# triac.net
KiCad netlist of a schematic drawn in EAGLE
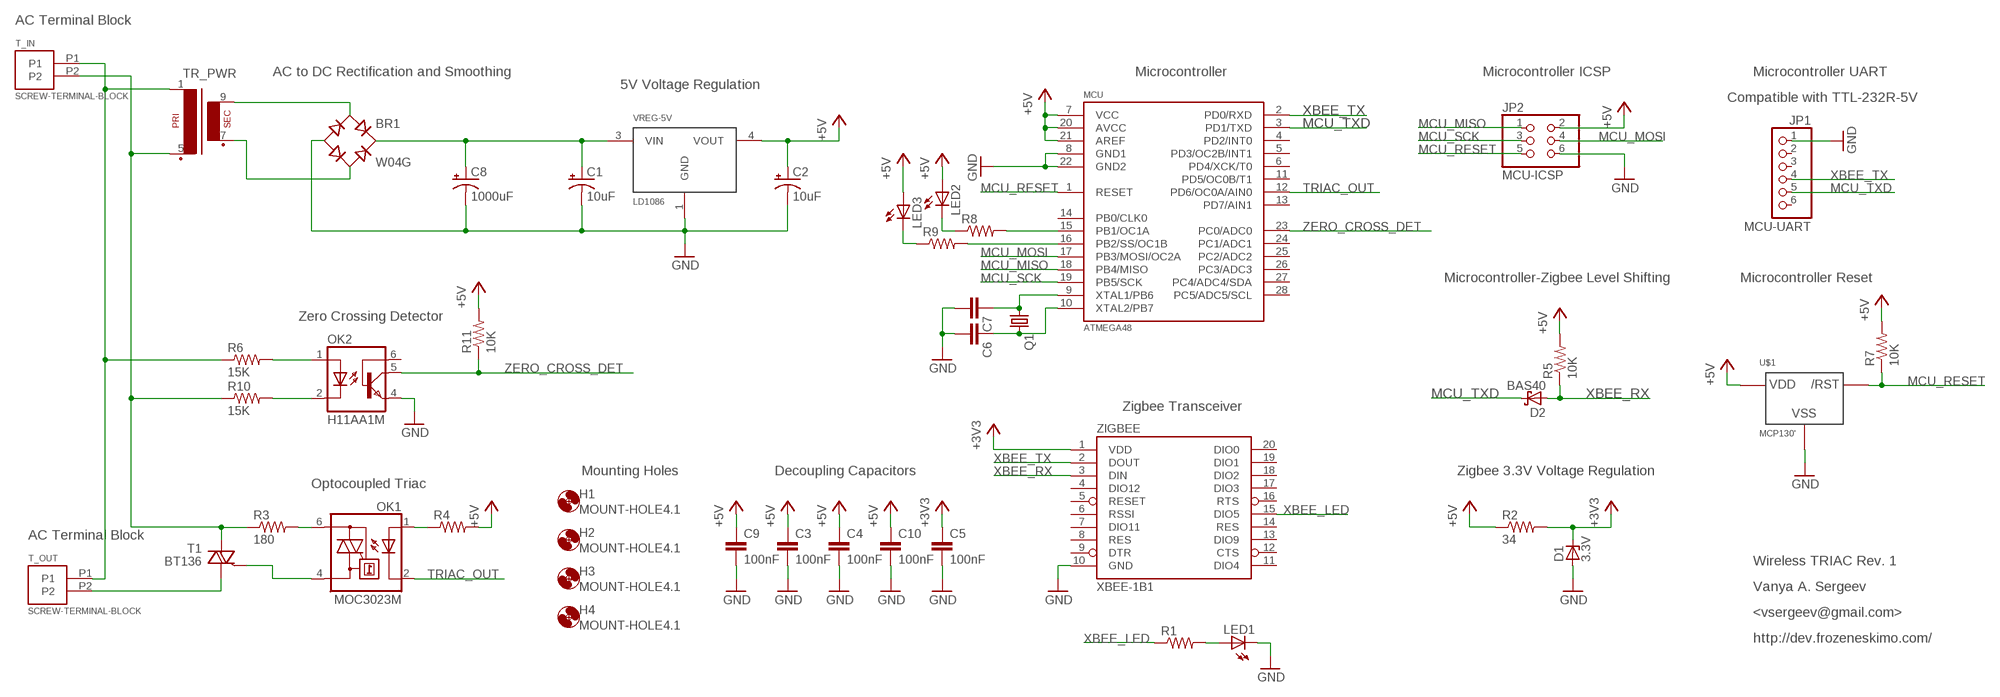
[diagram p0: schematic, sheet 1]

(export (version "E")
  (design (tool "Eeschema 10.0.6"))
  (components
    (comp (ref "BR1")
      (value "W04G")
      (footprint "eagle-import:WOG")
      (libsource (lib "eagle-import") (part "WG04"))
    )
    (comp (ref "C1")
      (value "10uF")
      (footprint "eagle-import:E2,5-5")
      (libsource (lib "eagle-import") (part "CPOL-USE2.5-5"))
    )
    (comp (ref "C2")
      (value "10uF")
      (footprint "eagle-import:E2,5-5")
      (libsource (lib "eagle-import") (part "CPOL-USE2.5-5"))
    )
    (comp (ref "C3")
      (value "100nF")
      (footprint "eagle-import:C0805")
      (libsource (lib "eagle-import") (part "C-EUC0805"))
    )
    (comp (ref "C4")
      (value "100nF")
      (footprint "eagle-import:C0805")
      (libsource (lib "eagle-import") (part "C-EUC0805"))
    )
    (comp (ref "C5")
      (value "100nF")
      (footprint "eagle-import:C0805")
      (libsource (lib "eagle-import") (part "C-EUC0805"))
    )
    (comp (ref "C6")
      (value "C-EUC0805")
      (footprint "eagle-import:C0805")
      (libsource (lib "eagle-import") (part "C-EUC0805"))
    )
    (comp (ref "C7")
      (value "C-EUC0805")
      (footprint "eagle-import:C0805")
      (libsource (lib "eagle-import") (part "C-EUC0805"))
    )
    (comp (ref "C8")
      (value "1000uF")
      (footprint "eagle-import:E5-13")
      (libsource (lib "eagle-import") (part "CPOL-USE5-13"))
    )
    (comp (ref "C9")
      (value "100nF")
      (footprint "eagle-import:C0805")
      (libsource (lib "eagle-import") (part "C-EUC0805"))
    )
    (comp (ref "C10")
      (value "100nF")
      (footprint "eagle-import:C0805")
      (libsource (lib "eagle-import") (part "C-EUC0805"))
    )
    (comp (ref "D1")
      (value "3.3V")
      (footprint "eagle-import:SOT23")
      (libsource (lib "eagle-import") (part "ZENER-DIODESOT23"))
    )
    (comp (ref "D2")
      (value "BAS40")
      (footprint "eagle-import:SOT23")
      (libsource (lib "eagle-import") (part "BAS40"))
    )
    (comp (ref "H1")
      (value "MOUNT-HOLE4.1")
      (footprint "eagle-import:4,1")
      (libsource (lib "eagle-import") (part "MOUNT-HOLE4.1"))
    )
    (comp (ref "H2")
      (value "MOUNT-HOLE4.1")
      (footprint "eagle-import:4,1")
      (libsource (lib "eagle-import") (part "MOUNT-HOLE4.1"))
    )
    (comp (ref "H3")
      (value "MOUNT-HOLE4.1")
      (footprint "eagle-import:4,1")
      (libsource (lib "eagle-import") (part "MOUNT-HOLE4.1"))
    )
    (comp (ref "H4")
      (value "MOUNT-HOLE4.1")
      (footprint "eagle-import:4,1")
      (libsource (lib "eagle-import") (part "MOUNT-HOLE4.1"))
    )
    (comp (ref "JP1")
      (value "MCU-UART")
      (footprint "eagle-import:1X06")
      (libsource (lib "eagle-import") (part "PINHD-1X6"))
    )
    (comp (ref "JP2")
      (value "MCU-ICSP")
      (footprint "eagle-import:2X03")
      (libsource (lib "eagle-import") (part "PINHD-2X3"))
    )
    (comp (ref "LED1")
      (value "LEDCHIPLED_0805")
      (footprint "eagle-import:CHIPLED_0805")
      (libsource (lib "eagle-import") (part "LEDCHIPLED_0805"))
    )
    (comp (ref "LED2")
      (value "LEDCHIPLED_0805")
      (footprint "eagle-import:CHIPLED_0805")
      (libsource (lib "eagle-import") (part "LEDCHIPLED_0805"))
    )
    (comp (ref "LED3")
      (value "LEDCHIPLED_0805")
      (footprint "eagle-import:CHIPLED_0805")
      (libsource (lib "eagle-import") (part "LEDCHIPLED_0805"))
    )
    (comp (ref "MCU")
      (value "ATMEGA48")
      (footprint "eagle-import:DIL28-3")
      (libsource (lib "eagle-import") (part "ATMEGA48"))
    )
    (comp (ref "OK1")
      (value "MOC3023M")
      (footprint "eagle-import:DIL06")
      (libsource (lib "eagle-import") (part "MOC30M23"))
    )
    (comp (ref "OK2")
      (value "H11AA1M")
      (footprint "eagle-import:DIL06")
      (libsource (lib "eagle-import") (part "H11A?M1"))
    )
    (comp (ref "Q1")
      (value "CRYSTALHC49UP")
      (footprint "eagle-import:HC49UP")
      (libsource (lib "eagle-import") (part "CRYSTALHC49UP"))
    )
    (comp (ref "R1")
      (value "R-US_R0805")
      (footprint "eagle-import:R0805")
      (libsource (lib "eagle-import") (part "R-US_R0805"))
    )
    (comp (ref "R2")
      (value "34")
      (footprint "eagle-import:R0805")
      (libsource (lib "eagle-import") (part "R-US_R0805"))
    )
    (comp (ref "R3")
      (value "180")
      (footprint "eagle-import:0204_7")
      (libsource (lib "eagle-import") (part "R-US_0204/7"))
    )
    (comp (ref "R4")
      (value "R-US_R0805")
      (footprint "eagle-import:R0805")
      (libsource (lib "eagle-import") (part "R-US_R0805"))
    )
    (comp (ref "R5")
      (value "10K")
      (footprint "eagle-import:R0805")
      (libsource (lib "eagle-import") (part "R-US_R0805"))
    )
    (comp (ref "R6")
      (value "15K")
      (footprint "eagle-import:0204_7")
      (libsource (lib "eagle-import") (part "R-US_0204/7"))
    )
    (comp (ref "R7")
      (value "10K")
      (footprint "eagle-import:R0805")
      (libsource (lib "eagle-import") (part "R-US_R0805"))
    )
    (comp (ref "R8")
      (value "R-US_R0805")
      (footprint "eagle-import:R0805")
      (libsource (lib "eagle-import") (part "R-US_R0805"))
    )
    (comp (ref "R9")
      (value "R-US_R0805")
      (footprint "eagle-import:R0805")
      (libsource (lib "eagle-import") (part "R-US_R0805"))
    )
    (comp (ref "R10")
      (value "15K")
      (footprint "eagle-import:0204_7")
      (libsource (lib "eagle-import") (part "R-US_0204/7"))
    )
    (comp (ref "R11")
      (value "10K")
      (footprint "eagle-import:R0805")
      (libsource (lib "eagle-import") (part "R-US_R0805"))
    )
    (comp (ref "T1")
      (value "BT136")
      (footprint "eagle-import:TO220AB")
      (libsource (lib "eagle-import") (part "BT136"))
    )
    (comp (ref "TR_PWR")
      (value "EI30-1")
      (footprint "eagle-import:EI30-1")
      (libsource (lib "eagle-import") (part "EI30-1"))
    )
    (comp (ref "T_IN")
      (value "SCREW-TERMINAL-BLOCK")
      (footprint "eagle-import:TERMINAL-BLOCK")
      (libsource (lib "eagle-import") (part "SCREW-TERMINAL-BLOCK"))
    )
    (comp (ref "T_OUT")
      (value "SCREW-TERMINAL-BLOCK")
      (footprint "eagle-import:TERMINAL-BLOCK")
      (libsource (lib "eagle-import") (part "SCREW-TERMINAL-BLOCK"))
    )
    (comp (ref "U$1")
      (value "MCP130'")
      (footprint "eagle-import:TO92")
      (libsource (lib "eagle-import") (part "MCP130'"))
    )
    (comp (ref "VREG-5V")
      (value "LD1086")
      (footprint "eagle-import:DPACK")
      (libsource (lib "eagle-import") (part "LD1086"))
    )
    (comp (ref "ZIGBEE")
      (value "XBEE-1B1")
      (footprint "eagle-import:XBEE-1")
      (libsource (lib "eagle-import") (part "XBEE-1B1"))
    )
  )
  (nets
    (net (code "1") (name "+3V3") (class "Default")
      (node (ref "C5") (pin "1") (pinfunction "1_1") (pintype "passive"))
      (node (ref "D1") (pin "3") (pinfunction "C_3") (pintype "passive"))
      (node (ref "R2") (pin "2") (pinfunction "2_2") (pintype "passive"))
      (node (ref "ZIGBEE") (pin "1") (pinfunction "VDD_1") (pintype "power_in"))
    )
    (net (code "2") (name "+5V") (class "Default")
      (node (ref "C10") (pin "1") (pinfunction "1_1") (pintype "passive"))
      (node (ref "C2") (pin "+") (pinfunction "+_+") (pintype "passive"))
      (node (ref "C3") (pin "1") (pinfunction "1_1") (pintype "passive"))
      (node (ref "C4") (pin "1") (pinfunction "1_1") (pintype "passive"))
      (node (ref "C9") (pin "1") (pinfunction "1_1") (pintype "passive"))
      (node (ref "JP2") (pin "2") (pinfunction "2_2") (pintype "passive"))
      (node (ref "LED2") (pin "A") (pinfunction "A_A") (pintype "passive"))
      (node (ref "LED3") (pin "A") (pinfunction "A_A") (pintype "passive"))
      (node (ref "MCU") (pin "20") (pinfunction "AVCC_20") (pintype "bidirectional"))
      (node (ref "MCU") (pin "21") (pinfunction "AREF_21") (pintype "bidirectional"))
      (node (ref "MCU") (pin "7") (pinfunction "VCC_7") (pintype "bidirectional"))
      (node (ref "R11") (pin "2") (pinfunction "2_2") (pintype "passive"))
      (node (ref "R2") (pin "1") (pinfunction "1_1") (pintype "passive"))
      (node (ref "R4") (pin "2") (pinfunction "2_2") (pintype "passive"))
      (node (ref "R5") (pin "2") (pinfunction "2_2") (pintype "passive"))
      (node (ref "R7") (pin "2") (pinfunction "2_2") (pintype "passive"))
      (node (ref "U$1") (pin "2") (pinfunction "VDD_2") (pintype "bidirectional"))
      (node (ref "VREG-5V") (pin "4") (pinfunction "VOUT_4") (pintype "bidirectional"))
    )
    (net (code "3") (name "/MCU_MISO") (class "Default")
      (node (ref "JP2") (pin "1") (pinfunction "1_1") (pintype "passive"))
      (node (ref "MCU") (pin "18") (pinfunction "PB4/MISO_18") (pintype "bidirectional"))
    )
    (net (code "4") (name "/MCU_MOSI") (class "Default")
      (node (ref "JP2") (pin "4") (pinfunction "4_4") (pintype "passive"))
      (node (ref "MCU") (pin "17") (pinfunction "PB3/MOSI/OC2A_17") (pintype "bidirectional"))
    )
    (net (code "5") (name "/MCU_RESET") (class "Default")
      (node (ref "JP2") (pin "5") (pinfunction "5_5") (pintype "passive"))
      (node (ref "MCU") (pin "1") (pinfunction "RESET_1") (pintype "bidirectional"))
      (node (ref "R7") (pin "1") (pinfunction "1_1") (pintype "passive"))
      (node (ref "U$1") (pin "1") (pinfunction "/RST_1") (pintype "bidirectional"))
    )
    (net (code "6") (name "/MCU_SCK") (class "Default")
      (node (ref "JP2") (pin "3") (pinfunction "3_3") (pintype "passive"))
      (node (ref "MCU") (pin "19") (pinfunction "PB5/SCK_19") (pintype "bidirectional"))
    )
    (net (code "7") (name "/MCU_TXD") (class "Default")
      (node (ref "D2") (pin "3") (pinfunction "C_3") (pintype "passive"))
      (node (ref "JP1") (pin "5") (pinfunction "5_5") (pintype "passive"))
      (node (ref "MCU") (pin "3") (pinfunction "PD1/TXD_3") (pintype "bidirectional"))
    )
    (net (code "8") (name "/TRIAC_OUT") (class "Default")
      (node (ref "MCU") (pin "12") (pinfunction "PD6/OC0A/AIN0_12") (pintype "bidirectional"))
      (node (ref "OK1") (pin "2") (pinfunction "C_2") (pintype "passive"))
    )
    (net (code "9") (name "/XBEE_LED") (class "Default")
      (node (ref "R1") (pin "1") (pinfunction "1_1") (pintype "passive"))
      (node (ref "ZIGBEE") (pin "15") (pinfunction "DIO5_15") (pintype "bidirectional"))
    )
    (net (code "10") (name "/XBEE_RX") (class "Default")
      (node (ref "D2") (pin "1") (pinfunction "A_1") (pintype "passive"))
      (node (ref "R5") (pin "1") (pinfunction "1_1") (pintype "passive"))
      (node (ref "ZIGBEE") (pin "3") (pinfunction "DIN_3") (pintype "input"))
    )
    (net (code "11") (name "/XBEE_TX") (class "Default")
      (node (ref "JP1") (pin "4") (pinfunction "4_4") (pintype "passive"))
      (node (ref "MCU") (pin "2") (pinfunction "PD0/RXD_2") (pintype "bidirectional"))
      (node (ref "ZIGBEE") (pin "2") (pinfunction "DOUT_2") (pintype "output"))
    )
    (net (code "12") (name "/ZERO_CROSS_DET") (class "Default")
      (node (ref "MCU") (pin "23") (pinfunction "PC0/ADC0_23") (pintype "bidirectional"))
      (node (ref "OK2") (pin "5") (pinfunction "COL_5") (pintype "passive"))
      (node (ref "R11") (pin "1") (pinfunction "1_1") (pintype "passive"))
    )
    (net (code "13") (name "GND") (class "Default")
      (node (ref "BR1") (pin "-") (pinfunction "-_-") (pintype "passive"))
      (node (ref "C1") (pin "-") (pinfunction "-_-") (pintype "passive"))
      (node (ref "C10") (pin "2") (pinfunction "2_2") (pintype "passive"))
      (node (ref "C2") (pin "-") (pinfunction "-_-") (pintype "passive"))
      (node (ref "C3") (pin "2") (pinfunction "2_2") (pintype "passive"))
      (node (ref "C4") (pin "2") (pinfunction "2_2") (pintype "passive"))
      (node (ref "C5") (pin "2") (pinfunction "2_2") (pintype "passive"))
      (node (ref "C6") (pin "2") (pinfunction "2_2") (pintype "passive"))
      (node (ref "C7") (pin "2") (pinfunction "2_2") (pintype "passive"))
      (node (ref "C8") (pin "-") (pinfunction "-_-") (pintype "passive"))
      (node (ref "C9") (pin "2") (pinfunction "2_2") (pintype "passive"))
      (node (ref "D1") (pin "1") (pinfunction "A_1") (pintype "passive"))
      (node (ref "JP1") (pin "1") (pinfunction "1_1") (pintype "passive"))
      (node (ref "JP2") (pin "6") (pinfunction "6_6") (pintype "passive"))
      (node (ref "LED1") (pin "C") (pinfunction "C_C") (pintype "passive"))
      (node (ref "MCU") (pin "22") (pinfunction "GND2_22") (pintype "bidirectional"))
      (node (ref "MCU") (pin "8") (pinfunction "GND1_8") (pintype "bidirectional"))
      (node (ref "OK2") (pin "4") (pinfunction "EMI_4") (pintype "passive"))
      (node (ref "U$1") (pin "3") (pinfunction "VSS_3") (pintype "bidirectional"))
      (node (ref "VREG-5V") (pin "1") (pinfunction "GND_1") (pintype "bidirectional"))
      (node (ref "ZIGBEE") (pin "10") (pinfunction "GND_10") (pintype "power_in"))
    )
    (net (code "14") (name "Net-(LED1-PadA)") (class "Default")
      (node (ref "LED1") (pin "A") (pinfunction "A_A") (pintype "passive"))
      (node (ref "R1") (pin "2") (pinfunction "2_2") (pintype "passive"))
    )
    (net (code "15") (name "Net-(LED2-PadC)") (class "Default")
      (node (ref "LED2") (pin "C") (pinfunction "C_C") (pintype "passive"))
      (node (ref "R8") (pin "1") (pinfunction "1_1") (pintype "passive"))
    )
    (net (code "16") (name "Net-(LED3-PadC)") (class "Default")
      (node (ref "LED3") (pin "C") (pinfunction "C_C") (pintype "passive"))
      (node (ref "R9") (pin "1") (pinfunction "1_1") (pintype "passive"))
    )
    (net (code "17") (name "Net-(MCU-PB1{slash}OC1A)") (class "Default")
      (node (ref "MCU") (pin "15") (pinfunction "PB1/OC1A_15") (pintype "bidirectional"))
      (node (ref "R8") (pin "2") (pinfunction "2_2") (pintype "passive"))
    )
    (net (code "18") (name "Net-(MCU-PB2{slash}SS{slash}OC1B)") (class "Default")
      (node (ref "MCU") (pin "16") (pinfunction "PB2/SS/OC1B_16") (pintype "bidirectional"))
      (node (ref "R9") (pin "2") (pinfunction "2_2") (pintype "passive"))
    )
    (net (code "19") (name "Net-(MCU-XTAL1{slash}PB6)") (class "Default")
      (node (ref "C7") (pin "1") (pinfunction "1_1") (pintype "passive"))
      (node (ref "MCU") (pin "9") (pinfunction "XTAL1/PB6_9") (pintype "bidirectional"))
      (node (ref "Q1") (pin "1") (pinfunction "1_1") (pintype "passive"))
    )
    (net (code "20") (name "Net-(MCU-XTAL2{slash}PB7)") (class "Default")
      (node (ref "C6") (pin "1") (pinfunction "1_1") (pintype "passive"))
      (node (ref "MCU") (pin "10") (pinfunction "XTAL2/PB7_10") (pintype "bidirectional"))
      (node (ref "Q1") (pin "2") (pinfunction "2_2") (pintype "passive"))
    )
    (net (code "21") (name "Net-(OK1-A)") (class "Default")
      (node (ref "OK1") (pin "1") (pinfunction "A_1") (pintype "passive"))
      (node (ref "R4") (pin "1") (pinfunction "1_1") (pintype "passive"))
    )
    (net (code "22") (name "Net-(OK1-A1)") (class "Default")
      (node (ref "OK1") (pin "4") (pinfunction "A1_4") (pintype "passive"))
      (node (ref "T1") (pin "3") (pinfunction "G_3") (pintype "passive"))
    )
    (net (code "23") (name "Net-(OK1-A2)") (class "Default")
      (node (ref "OK1") (pin "6") (pinfunction "A2_6") (pintype "passive"))
      (node (ref "R3") (pin "2") (pinfunction "2_2") (pintype "passive"))
    )
    (net (code "24") (name "Net-(OK2-A)") (class "Default")
      (node (ref "OK2") (pin "1") (pinfunction "A_1") (pintype "passive"))
      (node (ref "R6") (pin "2") (pinfunction "2_2") (pintype "passive"))
    )
    (net (code "25") (name "Net-(OK2-C)") (class "Default")
      (node (ref "OK2") (pin "2") (pinfunction "C_2") (pintype "passive"))
      (node (ref "R10") (pin "2") (pinfunction "2_2") (pintype "passive"))
    )
    (net (code "26") (name "Net-(T1-A1)") (class "Default")
      (node (ref "T1") (pin "1") (pinfunction "A1_1") (pintype "passive"))
      (node (ref "T_OUT") (pin "P2") (pinfunction "P2_P2") (pintype "bidirectional"))
    )
    (net (code "27") (name "Net-(T1-A2)") (class "Default")
      (node (ref "R10") (pin "1") (pinfunction "1_1") (pintype "passive"))
      (node (ref "R3") (pin "1") (pinfunction "1_1") (pintype "passive"))
      (node (ref "T1") (pin "2") (pinfunction "A2_2") (pintype "passive"))
      (node (ref "TR_PWR") (pin "5") (pinfunction "P2_5") (pintype "passive"))
      (node (ref "T_IN") (pin "P2") (pinfunction "P2_P2") (pintype "bidirectional"))
    )
    (net (code "28") (name "Net-(TR_PWR-P1)") (class "Default")
      (node (ref "R6") (pin "1") (pinfunction "1_1") (pintype "passive"))
      (node (ref "TR_PWR") (pin "1") (pinfunction "P1_1") (pintype "passive"))
      (node (ref "T_IN") (pin "P1") (pinfunction "P1_P1") (pintype "bidirectional"))
      (node (ref "T_OUT") (pin "P1") (pinfunction "P1_P1") (pintype "bidirectional"))
    )
    (net (code "29") (name "Net-(TR_PWR-S3)") (class "Default")
      (node (ref "BR1") (pin "AC2") (pinfunction "AC2_AC2") (pintype "passive"))
      (node (ref "TR_PWR") (pin "7") (pinfunction "S3_7") (pintype "passive"))
    )
    (net (code "30") (name "Net-(TR_PWR-S4)") (class "Default")
      (node (ref "BR1") (pin "AC1") (pinfunction "AC1_AC1") (pintype "passive"))
      (node (ref "TR_PWR") (pin "9") (pinfunction "S4_9") (pintype "passive"))
    )
    (net (code "31") (name "Net-(VREG-5V-VIN)") (class "Default")
      (node (ref "BR1") (pin "+") (pinfunction "+_+") (pintype "passive"))
      (node (ref "C1") (pin "+") (pinfunction "+_+") (pintype "passive"))
      (node (ref "C8") (pin "+") (pinfunction "+_+") (pintype "passive"))
      (node (ref "VREG-5V") (pin "3") (pinfunction "VIN_3") (pintype "bidirectional"))
    )
    (net (code "32") (name "unconnected-(JP1-Pad2)") (class "Default")
      (node (ref "JP1") (pin "2") (pinfunction "2_2") (pintype "passive"))
    )
    (net (code "33") (name "unconnected-(JP1-Pad3)") (class "Default")
      (node (ref "JP1") (pin "3") (pinfunction "3_3") (pintype "passive"))
    )
    (net (code "34") (name "unconnected-(JP1-Pad6)") (class "Default")
      (node (ref "JP1") (pin "6") (pinfunction "6_6") (pintype "passive"))
    )
    (net (code "35") (name "unconnected-(MCU-PB0{slash}CLK0-Pad14)") (class "Default")
      (node (ref "MCU") (pin "14") (pinfunction "PB0/CLK0_14") (pintype "bidirectional"))
    )
    (net (code "36") (name "unconnected-(MCU-PC1{slash}ADC1-Pad24)") (class "Default")
      (node (ref "MCU") (pin "24") (pinfunction "PC1/ADC1_24") (pintype "bidirectional"))
    )
    (net (code "37") (name "unconnected-(MCU-PC2{slash}ADC2-Pad25)") (class "Default")
      (node (ref "MCU") (pin "25") (pinfunction "PC2/ADC2_25") (pintype "bidirectional"))
    )
    (net (code "38") (name "unconnected-(MCU-PC3{slash}ADC3-Pad26)") (class "Default")
      (node (ref "MCU") (pin "26") (pinfunction "PC3/ADC3_26") (pintype "bidirectional"))
    )
    (net (code "39") (name "unconnected-(MCU-PC4{slash}ADC4{slash}SDA-Pad27)") (class "Default")
      (node (ref "MCU") (pin "27") (pinfunction "PC4/ADC4/SDA_27") (pintype "bidirectional"))
    )
    (net (code "40") (name "unconnected-(MCU-PC5{slash}ADC5{slash}SCL-Pad28)") (class "Default")
      (node (ref "MCU") (pin "28") (pinfunction "PC5/ADC5/SCL_28") (pintype "bidirectional"))
    )
    (net (code "41") (name "unconnected-(MCU-PD2{slash}INT0-Pad4)") (class "Default")
      (node (ref "MCU") (pin "4") (pinfunction "PD2/INT0_4") (pintype "bidirectional"))
    )
    (net (code "42") (name "unconnected-(MCU-PD3{slash}OC2B{slash}INT1-Pad5)") (class "Default")
      (node (ref "MCU") (pin "5") (pinfunction "PD3/OC2B/INT1_5") (pintype "bidirectional"))
    )
    (net (code "43") (name "unconnected-(MCU-PD4{slash}XCK{slash}T0-Pad6)") (class "Default")
      (node (ref "MCU") (pin "6") (pinfunction "PD4/XCK/T0_6") (pintype "bidirectional"))
    )
    (net (code "44") (name "unconnected-(MCU-PD5{slash}OC0B{slash}T1-Pad11)") (class "Default")
      (node (ref "MCU") (pin "11") (pinfunction "PD5/OC0B/T1_11") (pintype "bidirectional"))
    )
    (net (code "45") (name "unconnected-(MCU-PD7{slash}AIN1-Pad13)") (class "Default")
      (node (ref "MCU") (pin "13") (pinfunction "PD7/AIN1_13") (pintype "bidirectional"))
    )
    (net (code "46") (name "unconnected-(OK2-BAS-Pad6)") (class "Default")
      (node (ref "OK2") (pin "6") (pinfunction "BAS_6") (pintype "passive"))
    )
    (net (code "47") (name "unconnected-(ZIGBEE-CTS-Pad12)") (class "Default")
      (node (ref "ZIGBEE") (pin "12") (pinfunction "CTS_12") (pintype "output"))
    )
    (net (code "48") (name "unconnected-(ZIGBEE-DIO0-Pad20)") (class "Default")
      (node (ref "ZIGBEE") (pin "20") (pinfunction "DIO0_20") (pintype "bidirectional"))
    )
    (net (code "49") (name "unconnected-(ZIGBEE-DIO1-Pad19)") (class "Default")
      (node (ref "ZIGBEE") (pin "19") (pinfunction "DIO1_19") (pintype "bidirectional"))
    )
    (net (code "50") (name "unconnected-(ZIGBEE-DIO2-Pad18)") (class "Default")
      (node (ref "ZIGBEE") (pin "18") (pinfunction "DIO2_18") (pintype "bidirectional"))
    )
    (net (code "51") (name "unconnected-(ZIGBEE-DIO3-Pad17)") (class "Default")
      (node (ref "ZIGBEE") (pin "17") (pinfunction "DIO3_17") (pintype "bidirectional"))
    )
    (net (code "52") (name "unconnected-(ZIGBEE-DIO4-Pad11)") (class "Default")
      (node (ref "ZIGBEE") (pin "11") (pinfunction "DIO4_11") (pintype "bidirectional"))
    )
    (net (code "53") (name "unconnected-(ZIGBEE-DIO9-Pad13)") (class "Default")
      (node (ref "ZIGBEE") (pin "13") (pinfunction "DIO9_13") (pintype "bidirectional"))
    )
    (net (code "54") (name "unconnected-(ZIGBEE-DIO11-Pad7)") (class "Default")
      (node (ref "ZIGBEE") (pin "7") (pinfunction "DIO11_7") (pintype "bidirectional"))
    )
    (net (code "55") (name "unconnected-(ZIGBEE-DIO12-Pad4)") (class "Default")
      (node (ref "ZIGBEE") (pin "4") (pinfunction "DIO12_4") (pintype "bidirectional"))
    )
    (net (code "56") (name "unconnected-(ZIGBEE-DTR-Pad9)") (class "Default")
      (node (ref "ZIGBEE") (pin "9") (pinfunction "DTR_9") (pintype "bidirectional"))
    )
    (net (code "57") (name "unconnected-(ZIGBEE-RES-Pad8)") (class "Default")
      (node (ref "ZIGBEE") (pin "8") (pinfunction "RES_8") (pintype "bidirectional"))
    )
    (net (code "58") (name "unconnected-(ZIGBEE-RES-Pad14)") (class "Default")
      (node (ref "ZIGBEE") (pin "14") (pinfunction "RES_14") (pintype "bidirectional"))
    )
    (net (code "59") (name "unconnected-(ZIGBEE-RESET-Pad5)") (class "Default")
      (node (ref "ZIGBEE") (pin "5") (pinfunction "RESET_5") (pintype "input"))
    )
    (net (code "60") (name "unconnected-(ZIGBEE-RSSI-Pad6)") (class "Default")
      (node (ref "ZIGBEE") (pin "6") (pinfunction "RSSI_6") (pintype "bidirectional"))
    )
    (net (code "61") (name "unconnected-(ZIGBEE-RTS-Pad16)") (class "Default")
      (node (ref "ZIGBEE") (pin "16") (pinfunction "RTS_16") (pintype "input"))
    )
  )
)
